# Sheet1.net
KiCad netlist of a schematic drawn in Altium Designer
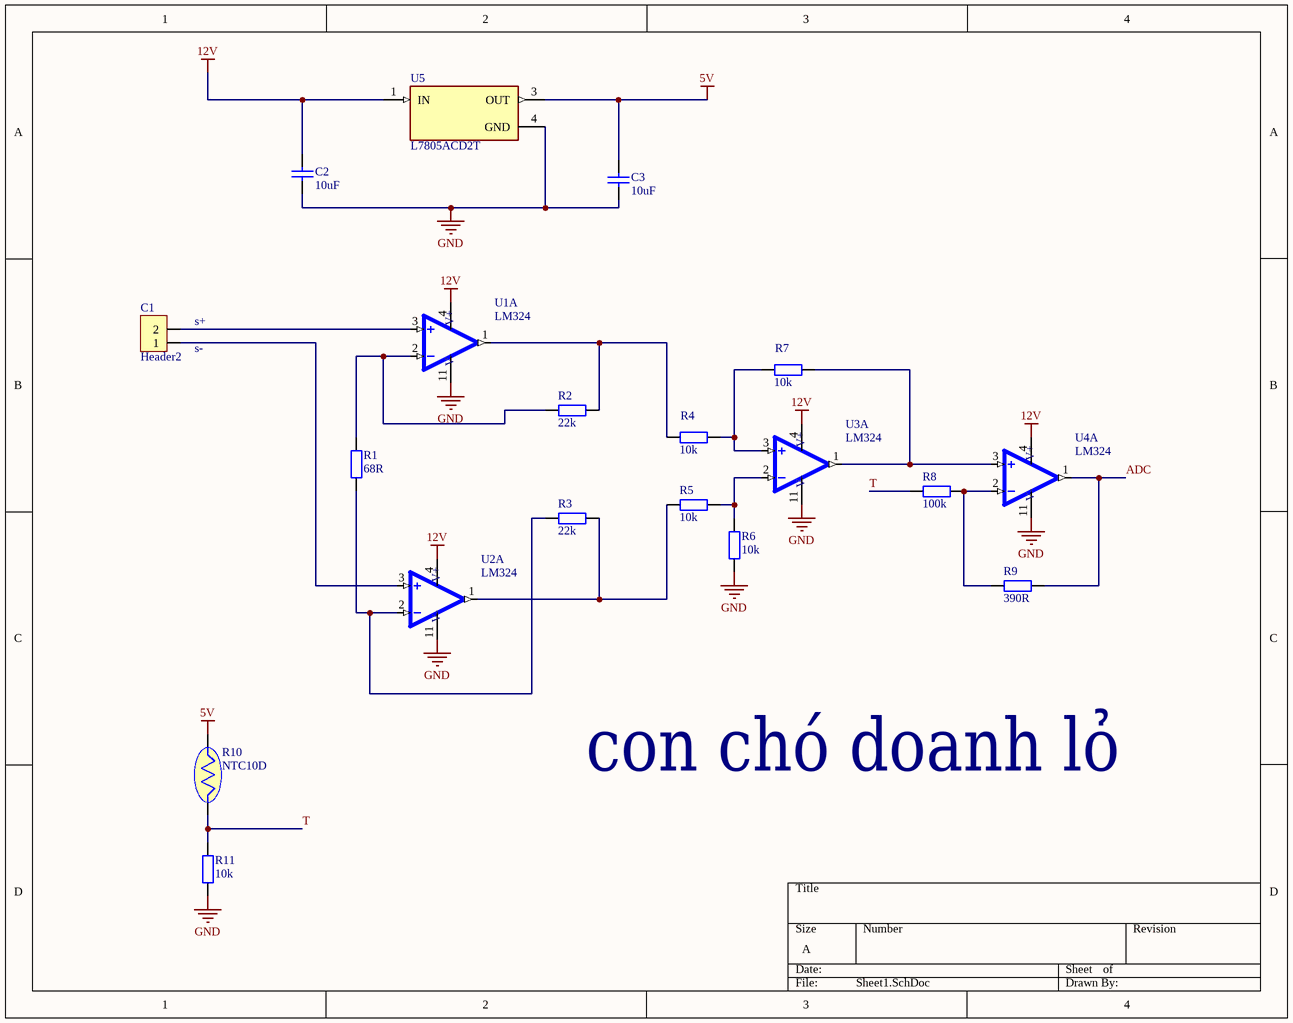
[diagram p0: Sheet1.SchDoc]

(export (version "E")
  (design (tool "Eeschema 10.0.6"))
  (components
    (comp (ref "C1")
      (value "Header2")
      (footprint "HDR2")
      (description "Header IDC, 2 x 1 Pin Vertical 2.54mm Pitch (Non-Boxed, Male)")
      (fields
        (field (name "MANUFACTURER") "Würth Elektronik eiSos GmbH")
        (field (name "PARTNO") "613002143121")
        (field (name "CREATED BY") "Karrer Zheng")
      )
      (libsource (lib "Altium Library") (part "Header2"))
    )
    (comp (ref "C2")
      (value "10uF")
      (footprint "tu 0805")
      (description "Dán")
      (libsource (lib "Capacitor") (part "Tu 0805 221 50V"))
    )
    (comp (ref "C3")
      (value "10uF")
      (footprint "tu 0805")
      (description "Dán")
      (libsource (lib "Capacitor") (part "Tu 0805 221 50V"))
    )
    (comp (ref "R1")
      (value "68R")
      (footprint "Tro SMD 0805")
      (description "Dán")
      (libsource (lib "Resistor") (part "Tro 0805 5% 68R"))
    )
    (comp (ref "R2")
      (value "22k")
      (footprint "tro smd 0805")
      (description "Dán")
      (libsource (lib "Resistor") (part "Tro 0805 5% 22k"))
    )
    (comp (ref "R3")
      (value "22k")
      (footprint "tro smd 0805")
      (description "Dán")
      (libsource (lib "Resistor") (part "Tro 0805 5% 22k"))
    )
    (comp (ref "R4")
      (value "10k")
      (footprint "tro smd 0805")
      (description "Dán")
      (libsource (lib "Resistor") (part "Tro 0805 5% 10k"))
    )
    (comp (ref "R5")
      (value "10k")
      (footprint "tro smd 0805")
      (description "Dán")
      (libsource (lib "Resistor") (part "Tro 0805 5% 10k"))
    )
    (comp (ref "R6")
      (value "10k")
      (footprint "tro smd 0805")
      (description "Dán")
      (libsource (lib "Resistor") (part "Tro 0805 5% 10k"))
    )
    (comp (ref "R7")
      (value "10k")
      (footprint "tro smd 0805")
      (description "Dán")
      (libsource (lib "Resistor") (part "Tro 0805 5% 10k"))
    )
    (comp (ref "R8")
      (value "100k")
      (footprint "tro smd 0805")
      (description "Dán")
      (libsource (lib "Resistor") (part "Tro 0805 5% 100k"))
    )
    (comp (ref "R9")
      (value "390R")
      (footprint "Tro SMD 0805")
      (description "Dán")
      (libsource (lib "Resistor") (part "Tro 0805 5% 390R"))
    )
    (comp (ref "R10") (value "NTC10D") (footprint "NTC10D") (libsource (lib "Cty1") (part "NTC10D")))
    (comp (ref "R11")
      (value "10k")
      (footprint "tro smd 0805")
      (description "Dán")
      (libsource (lib "Resistor") (part "Tro 0805 5% 10k"))
    )
    (comp (ref "U1")
      (value "LM324")
      (footprint "SOIC127P600X175-14N")
      (description "Op Amp Quad DÃ¼ÅŸÃ¼k VoltajlÄ± AmplifikatÃ¶r Â±2.75V/5.5V 14-Pin SOIC T/R")
      (fields (field (name "MF") "Intersil") (field (name "MP") "LM324.."))
      (libsource (lib "LM324 (1)") (part "LM324"))
    )
    (comp (ref "U2")
      (value "LM324")
      (footprint "SOIC127P600X175-14N")
      (description "Op Amp Quad DÃ¼ÅŸÃ¼k VoltajlÄ± AmplifikatÃ¶r Â±2.75V/5.5V 14-Pin SOIC T/R")
      (fields (field (name "MF") "Intersil") (field (name "MP") "LM324.."))
      (libsource (lib "LM324 (1)") (part "LM324"))
    )
    (comp (ref "U3")
      (value "LM324")
      (footprint "SOIC127P600X175-14N")
      (description "Op Amp Quad DÃ¼ÅŸÃ¼k VoltajlÄ± AmplifikatÃ¶r Â±2.75V/5.5V 14-Pin SOIC T/R")
      (fields (field (name "MF") "Intersil") (field (name "MP") "LM324.."))
      (libsource (lib "LM324 (1)") (part "LM324"))
    )
    (comp (ref "U4")
      (value "LM324")
      (footprint "SOIC127P600X175-14N")
      (description "Op Amp Quad DÃ¼ÅŸÃ¼k VoltajlÄ± AmplifikatÃ¶r Â±2.75V/5.5V 14-Pin SOIC T/R")
      (fields (field (name "MF") "Intersil") (field (name "MP") "LM324.."))
      (libsource (lib "LM324 (1)") (part "LM324"))
    )
    (comp (ref "U5")
      (value "L7805ACD2T")
      (footprint "VREG_L7805ACD2T")
      (description "Linear Voltage Regulator IC Positive Fixed 1 Output 1.5A D2PAK")
      (fields (field (name "MF") "STMicroelectronics"))
      (libsource (lib "L7805ACD2T") (part "L7805ACD2T"))
    )
  )
  (nets
    (net (code "1") (name "/ADC") (class "Default")
      (node (ref "R9") (pin "2") (pinfunction "2_2") (pintype "passive"))
      (node (ref "U4") (pin "1") (pinfunction "OUTPUT1_1") (pintype "output"))
    )
    (net (code "2") (name "/T") (class "Default")
      (node (ref "R10") (pin "1") (pinfunction "1_1") (pintype "passive"))
      (node (ref "R11") (pin "2") (pinfunction "2_2") (pintype "passive"))
      (node (ref "R8") (pin "1") (pinfunction "1_1") (pintype "passive"))
    )
    (net (code "3") (name "5V") (class "Default")
      (node (ref "C3") (pin "1") (pinfunction "1_1") (pintype "passive"))
      (node (ref "R10") (pin "2") (pinfunction "2_2") (pintype "passive"))
      (node (ref "U5") (pin "3") (pinfunction "OUT_3") (pintype "output"))
    )
    (net (code "4") (name "12V") (class "Default")
      (node (ref "C2") (pin "1") (pinfunction "1_1") (pintype "passive"))
      (node (ref "U1") (pin "4") (pinfunction "VCC+_4") (pintype "power_in"))
      (node (ref "U2") (pin "4") (pinfunction "VCC+_4") (pintype "power_in"))
      (node (ref "U3") (pin "4") (pinfunction "VCC+_4") (pintype "power_in"))
      (node (ref "U4") (pin "4") (pinfunction "VCC+_4") (pintype "power_in"))
      (node (ref "U5") (pin "1") (pinfunction "IN_1") (pintype "input"))
    )
    (net (code "5") (name "GND") (class "Default")
      (node (ref "C2") (pin "2") (pinfunction "2_2") (pintype "passive"))
      (node (ref "C3") (pin "2") (pinfunction "2_2") (pintype "passive"))
      (node (ref "R11") (pin "1") (pinfunction "1_1") (pintype "passive"))
      (node (ref "R6") (pin "1") (pinfunction "1_1") (pintype "passive"))
      (node (ref "U1") (pin "11") (pinfunction "VCC-_11") (pintype "power_in"))
      (node (ref "U2") (pin "11") (pinfunction "VCC-_11") (pintype "power_in"))
      (node (ref "U3") (pin "11") (pinfunction "VCC-_11") (pintype "power_in"))
      (node (ref "U4") (pin "11") (pinfunction "VCC-_11") (pintype "power_in"))
      (node (ref "U5") (pin "4") (pinfunction "GND_4") (pintype "power_in"))
    )
    (net (code "6") (name "Net-(U1A-INVERTING_INPUT1)") (class "Default")
      (node (ref "R1") (pin "2") (pinfunction "2_2") (pintype "passive"))
      (node (ref "R2") (pin "1") (pinfunction "1_1") (pintype "passive"))
      (node (ref "U1") (pin "2") (pinfunction "INVERTING_INPUT1_2") (pintype "input"))
    )
    (net (code "7") (name "Net-(U1A-NON-INVERTING_INPUT1)") (class "Default")
      (node (ref "C1") (pin "2") (pinfunction "2_2") (pintype "passive"))
      (node (ref "U1") (pin "3") (pinfunction "NON-INVERTING_INPUT1_3") (pintype "input"))
    )
    (net (code "8") (name "Net-(U1A-OUTPUT1)") (class "Default")
      (node (ref "R2") (pin "2") (pinfunction "2_2") (pintype "passive"))
      (node (ref "R4") (pin "1") (pinfunction "1_1") (pintype "passive"))
      (node (ref "U1") (pin "1") (pinfunction "OUTPUT1_1") (pintype "output"))
    )
    (net (code "9") (name "Net-(U2A-INVERTING_INPUT1)") (class "Default")
      (node (ref "R1") (pin "1") (pinfunction "1_1") (pintype "passive"))
      (node (ref "R3") (pin "1") (pinfunction "1_1") (pintype "passive"))
      (node (ref "U2") (pin "2") (pinfunction "INVERTING_INPUT1_2") (pintype "input"))
    )
    (net (code "10") (name "Net-(U2A-NON-INVERTING_INPUT1)") (class "Default")
      (node (ref "C1") (pin "1") (pinfunction "1_1") (pintype "passive"))
      (node (ref "U2") (pin "3") (pinfunction "NON-INVERTING_INPUT1_3") (pintype "input"))
    )
    (net (code "11") (name "Net-(U2A-OUTPUT1)") (class "Default")
      (node (ref "R3") (pin "2") (pinfunction "2_2") (pintype "passive"))
      (node (ref "R5") (pin "1") (pinfunction "1_1") (pintype "passive"))
      (node (ref "U2") (pin "1") (pinfunction "OUTPUT1_1") (pintype "output"))
    )
    (net (code "12") (name "Net-(U3A-INVERTING_INPUT1)") (class "Default")
      (node (ref "R5") (pin "2") (pinfunction "2_2") (pintype "passive"))
      (node (ref "R6") (pin "2") (pinfunction "2_2") (pintype "passive"))
      (node (ref "U3") (pin "2") (pinfunction "INVERTING_INPUT1_2") (pintype "input"))
    )
    (net (code "13") (name "Net-(U3A-NON-INVERTING_INPUT1)") (class "Default")
      (node (ref "R4") (pin "2") (pinfunction "2_2") (pintype "passive"))
      (node (ref "R7") (pin "1") (pinfunction "1_1") (pintype "passive"))
      (node (ref "U3") (pin "3") (pinfunction "NON-INVERTING_INPUT1_3") (pintype "input"))
    )
    (net (code "14") (name "Net-(U3A-OUTPUT1)") (class "Default")
      (node (ref "R7") (pin "2") (pinfunction "2_2") (pintype "passive"))
      (node (ref "U3") (pin "1") (pinfunction "OUTPUT1_1") (pintype "output"))
      (node (ref "U4") (pin "3") (pinfunction "NON-INVERTING_INPUT1_3") (pintype "input"))
    )
    (net (code "15") (name "Net-(U4A-INVERTING_INPUT1)") (class "Default")
      (node (ref "R8") (pin "2") (pinfunction "2_2") (pintype "passive"))
      (node (ref "R9") (pin "1") (pinfunction "1_1") (pintype "passive"))
      (node (ref "U4") (pin "2") (pinfunction "INVERTING_INPUT1_2") (pintype "input"))
    )
  )
)
